# PWR_M_V1.net
KiCad netlist of a schematic drawn in Altium Designer
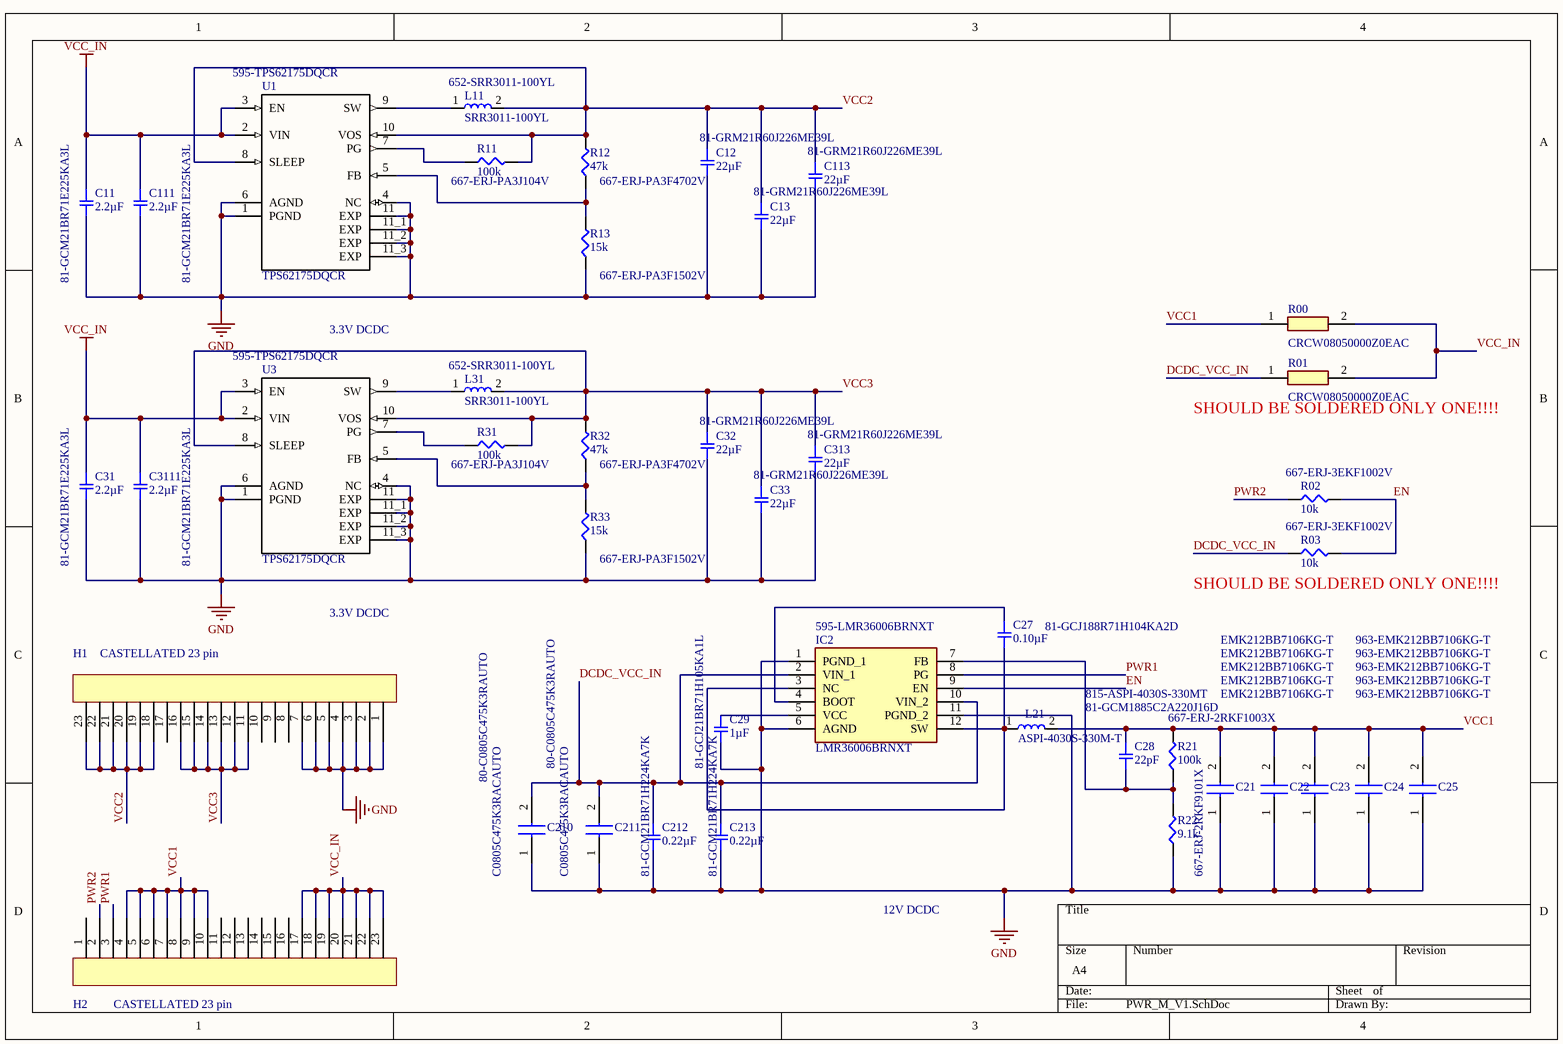
[diagram p0: PWR_M_V1.SchDoc]

(export (version "E")
  (design (tool "Eeschema 10.0.6"))
  (components
    (comp (ref "C11")
      (value "2.2µF")
      (footprint "SMD-0805C")
      (description "CAP CER 2.2UF 25V X7R 0805")
      (fields
        (field (name "DIGI-KEY PART NUMBER") "490-4787-1-ND")
        (field (name "PART NUMBER") "GCM21BR71E225KA73L")
        (field (name "SUPPLIER PART NUMBER 1") "81-GCM21BR71E225KA3L")
      )
      (libsource (lib "capacitor_murata_0805") (part "GCM21BR71E225KA73L"))
    )
    (comp (ref "C12")
      (value "22µF")
      (footprint "SMD-0805C")
      (description "CAP CER 22UF 6.3V X5R 0805")
      (fields
        (field (name "PART NUMBER") "GRM21BR60J226ME39L")
        (field (name "DIGI-KEY PART NUMBER") "490-1719-1-ND")
        (field (name "SUPPLIER PART NUMBER 1") "81-GRM21R60J226ME39L")
      )
      (libsource (lib "cap_murata") (part "CAPACITOR"))
    )
    (comp (ref "C13")
      (value "22µF")
      (footprint "SMD-0805C")
      (description "CAP CER 22UF 6.3V X5R 0805")
      (fields
        (field (name "PART NUMBER") "GRM21BR60J226ME39L")
        (field (name "DIGI-KEY PART NUMBER") "490-1719-1-ND")
        (field (name "SUPPLIER PART NUMBER 1") "81-GRM21R60J226ME39L")
      )
      (libsource (lib "cap_murata") (part "CAPACITOR"))
    )
    (comp (ref "C21")
      (value "EMK212BB7106KG-T")
      (footprint "SamacSys:CAPC2012X135N")
      (description "Capacitor")
      (fields (field (name "SUPPLIER PART NUMBER 1") "963-EMK212BB7106KG-T"))
      (libsource (lib "*") (part "EMK212BB7106KG-T"))
    )
    (comp (ref "C22")
      (value "EMK212BB7106KG-T")
      (footprint "SamacSys:CAPC2012X135N")
      (description "Capacitor")
      (fields (field (name "SUPPLIER PART NUMBER 1") "963-EMK212BB7106KG-T"))
      (libsource (lib "*") (part "EMK212BB7106KG-T"))
    )
    (comp (ref "C23")
      (value "EMK212BB7106KG-T")
      (footprint "SamacSys:CAPC2012X135N")
      (description "Capacitor")
      (fields (field (name "SUPPLIER PART NUMBER 1") "963-EMK212BB7106KG-T"))
      (libsource (lib "*") (part "EMK212BB7106KG-T"))
    )
    (comp (ref "C24")
      (value "EMK212BB7106KG-T")
      (footprint "SamacSys:CAPC2012X135N")
      (description "Capacitor")
      (fields (field (name "SUPPLIER PART NUMBER 1") "963-EMK212BB7106KG-T"))
      (libsource (lib "*") (part "EMK212BB7106KG-T"))
    )
    (comp (ref "C25")
      (value "EMK212BB7106KG-T")
      (footprint "SamacSys:CAPC2012X135N")
      (description "Capacitor")
      (fields (field (name "SUPPLIER PART NUMBER 1") "963-EMK212BB7106KG-T"))
      (libsource (lib "*") (part "EMK212BB7106KG-T"))
    )
    (comp (ref "C27")
      (value "0.10µF")
      (footprint "SMD-0603C")
      (description "CAP CER 0.1UF 50V X7R 0603")
      (fields
        (field (name "DIGI-KEY PART NUMBER") "490-5798-1-ND")
        (field (name "PART NUMBER") "GCJ188R71H104KA12D")
        (field (name "SUPPLIER PART NUMBER 1") "81-GCJ188R71H104KA2D")
      )
      (libsource (lib "capacitor_murata_0603") (part "GCJ188R71H104KA12D"))
    )
    (comp (ref "C28")
      (value "22pF")
      (footprint "SMD-0603C")
      (description "CAP CER 22PF 100V NP0 0603")
      (fields
        (field (name "DIGI-KEY PART NUMBER") "490-4942-1-ND")
        (field (name "PART NUMBER") "GCM1885C2A220JA16D")
        (field (name "SUPPLIER PART NUMBER 1") "81-GCM1885C2A220J16D")
      )
      (libsource (lib "capacitor_murata_0603") (part "GCM1885C2A220JA16D"))
    )
    (comp (ref "C29")
      (value "1µF")
      (footprint "SMD-0805C")
      (description "CAP CER 1UF 50V X7R 0805")
      (fields
        (field (name "DIGI-KEY PART NUMBER") "490-10667-1-ND")
        (field (name "PART NUMBER") "GCJ21BR71H105KA01L")
        (field (name "SUPPLIER PART NUMBER 1") "81-GCJ21BR71H105KA1L")
      )
      (libsource (lib "capacitor_murata_0805") (part "GCJ21BR71H105KA01L"))
    )
    (comp (ref "C31")
      (value "2.2µF")
      (footprint "SMD-0805C")
      (description "CAP CER 2.2UF 25V X7R 0805")
      (fields
        (field (name "DIGI-KEY PART NUMBER") "490-4787-1-ND")
        (field (name "PART NUMBER") "GCM21BR71E225KA73L")
        (field (name "SUPPLIER PART NUMBER 1") "81-GCM21BR71E225KA3L")
      )
      (libsource (lib "capacitor_murata_0805") (part "GCM21BR71E225KA73L"))
    )
    (comp (ref "C32")
      (value "22µF")
      (footprint "SMD-0805C")
      (description "CAP CER 22UF 6.3V X5R 0805")
      (fields
        (field (name "PART NUMBER") "GRM21BR60J226ME39L")
        (field (name "DIGI-KEY PART NUMBER") "490-1719-1-ND")
        (field (name "SUPPLIER PART NUMBER 1") "81-GRM21R60J226ME39L")
      )
      (libsource (lib "cap_murata") (part "CAPACITOR"))
    )
    (comp (ref "C33")
      (value "22µF")
      (footprint "SMD-0805C")
      (description "CAP CER 22UF 6.3V X5R 0805")
      (fields
        (field (name "PART NUMBER") "GRM21BR60J226ME39L")
        (field (name "DIGI-KEY PART NUMBER") "490-1719-1-ND")
        (field (name "SUPPLIER PART NUMBER 1") "81-GRM21R60J226ME39L")
      )
      (libsource (lib "cap_murata") (part "CAPACITOR"))
    )
    (comp (ref "C111")
      (value "2.2µF")
      (footprint "SMD-0805C")
      (description "CAP CER 2.2UF 25V X7R 0805")
      (fields
        (field (name "DIGI-KEY PART NUMBER") "490-4787-1-ND")
        (field (name "PART NUMBER") "GCM21BR71E225KA73L")
        (field (name "SUPPLIER PART NUMBER 1") "81-GCM21BR71E225KA3L")
      )
      (libsource (lib "capacitor_murata_0805") (part "GCM21BR71E225KA73L"))
    )
    (comp (ref "C113")
      (value "22µF")
      (footprint "SMD-0805C")
      (description "CAP CER 22UF 6.3V X5R 0805")
      (fields
        (field (name "PART NUMBER") "GRM21BR60J226ME39L")
        (field (name "DIGI-KEY PART NUMBER") "490-1719-1-ND")
        (field (name "SUPPLIER PART NUMBER 1") "81-GRM21R60J226ME39L")
      )
      (libsource (lib "cap_murata") (part "CAPACITOR"))
    )
    (comp (ref "C210")
      (value "C0805C475K3RACAUTO")
      (footprint "SamacSys:CAPC2012X125N")
      (description "Capacitor")
      (fields
        (field (name "MOUSER2 PART NUMBER") "80-C0805C475K3RAUTO")
        (field (name "SUPPLIER PART NUMBER 1") "80-C0805C475K3RAUTO")
      )
      (libsource (lib "*") (part "C0805C475K3RACAUTO"))
    )
    (comp (ref "C211")
      (value "C0805C475K3RACAUTO")
      (footprint "SamacSys:CAPC2012X125N")
      (description "Capacitor")
      (fields
        (field (name "MOUSER2 PART NUMBER") "80-C0805C475K3RAUTO")
        (field (name "SUPPLIER PART NUMBER 1") "80-C0805C475K3RAUTO")
      )
      (libsource (lib "*") (part "C0805C475K3RACAUTO"))
    )
    (comp (ref "C212")
      (value "0.22µF")
      (footprint "SMD-0805C")
      (description "CAP CER 0.22UF 50V X7R 0805")
      (fields
        (field (name "DIGI-KEY PART NUMBER") "490-13311-1-ND")
        (field (name "PART NUMBER") "GCM21BR71H224KA37K")
        (field (name "SUPPLIER PART NUMBER 1") "81-GCM21BR71H224KA7K")
      )
      (libsource (lib "capacitor_murata_0805") (part "GCM21BR71H224KA37K"))
    )
    (comp (ref "C213")
      (value "0.22µF")
      (footprint "SMD-0805C")
      (description "CAP CER 0.22UF 50V X7R 0805")
      (fields
        (field (name "DIGI-KEY PART NUMBER") "490-13311-1-ND")
        (field (name "PART NUMBER") "GCM21BR71H224KA37K")
        (field (name "SUPPLIER PART NUMBER 1") "81-GCM21BR71H224KA7K")
      )
      (libsource (lib "capacitor_murata_0805") (part "GCM21BR71H224KA37K"))
    )
    (comp (ref "C313")
      (value "22µF")
      (footprint "SMD-0805C")
      (description "CAP CER 22UF 6.3V X5R 0805")
      (fields
        (field (name "PART NUMBER") "GRM21BR60J226ME39L")
        (field (name "DIGI-KEY PART NUMBER") "490-1719-1-ND")
        (field (name "SUPPLIER PART NUMBER 1") "81-GRM21R60J226ME39L")
      )
      (libsource (lib "cap_murata") (part "CAPACITOR"))
    )
    (comp (ref "C3111")
      (value "2.2µF")
      (footprint "SMD-0805C")
      (description "CAP CER 2.2UF 25V X7R 0805")
      (fields
        (field (name "DIGI-KEY PART NUMBER") "490-4787-1-ND")
        (field (name "PART NUMBER") "GCM21BR71E225KA73L")
        (field (name "SUPPLIER PART NUMBER 1") "81-GCM21BR71E225KA3L")
      )
      (libsource (lib "capacitor_murata_0805") (part "GCM21BR71E225KA73L"))
    )
    (comp (ref "H1")
      (value "CASTELLATED 23 pin")
      (footprint "CASTELLATED 23 pin")
      (libsource (lib "USIB") (part "CASTELLATED 23 pin"))
    )
    (comp (ref "H2")
      (value "CASTELLATED 23 pin")
      (footprint "CASTELLATED 23 pin")
      (libsource (lib "") (part "CASTELLATED 23 pin_1"))
    )
    (comp (ref "IC2")
      (value "LMR36006BRNXT")
      (footprint "SamacSys:LMR36015FSCQRNXTQ1")
      (description "Integrated Circuit")
      (fields
        (field (name "MOUSER2 PART NUMBER") "595-LMR36006BRNXT")
        (field (name "SUPPLIER PART NUMBER 1") "595-LMR36006BRNXT")
      )
      (libsource (lib "*") (part "LMR36006BRNXT"))
    )
    (comp (ref "L11")
      (value "SRR3011-100YL")
      (footprint "SRR3011-100YL")
      (fields (field (name "SUPPLIER PART NUMBER 1") "652-SRR3011-100YL"))
      (libsource (lib "SRR3011-100YL") (part "SRR3011-100YL"))
    )
    (comp (ref "L21")
      (value "ASPI-4030S-330M-T")
      (footprint "INDPM4040X300N")
      (fields (field (name "SUPPLIER PART NUMBER 1") "815-ASPI-4030S-330MT"))
      (libsource (lib "SamacSys") (part "ASPI-4030S-330M-T"))
    )
    (comp (ref "L31")
      (value "SRR3011-100YL")
      (footprint "SRR3011-100YL")
      (fields (field (name "SUPPLIER PART NUMBER 1") "652-SRR3011-100YL"))
      (libsource (lib "SRR3011-100YL") (part "SRR3011-100YL"))
    )
    (comp (ref "R00")
      (value "CRCW08050000Z0EAC")
      (footprint "SamacSys:RESC2012X60N")
      (description "Resistor")
      (fields (field (name "MOUSER2 PART NUMBER") "71-CRCW08050000Z0EAC"))
      (libsource (lib "*") (part "CRCW08050000Z0EAC"))
    )
    (comp (ref "R01")
      (value "CRCW08050000Z0EAC")
      (footprint "SamacSys:RESC2012X60N")
      (description "Resistor")
      (fields (field (name "MOUSER2 PART NUMBER") "71-CRCW08050000Z0EAC"))
      (libsource (lib "*") (part "CRCW08050000Z0EAC"))
    )
    (comp (ref "R02")
      (value "10k")
      (footprint "SMD-0603-RES")
      (description "RES SMD 10K OHM 1% 1/10W 0603")
      (fields
        (field (name "PART NUMBER") "ERJ-3EKF1002V")
        (field (name "DIGI-KEY PART NUMBER") "P10.0KHCT-ND")
        (field (name "SUPPLIER PART NUMBER 1") "667-ERJ-3EKF1002V")
      )
      (libsource (lib "Panasonic_ERJ_0603") (part "ERJ-3EKF1002V"))
    )
    (comp (ref "R03")
      (value "10k")
      (footprint "SMD-0603-RES")
      (description "RES SMD 10K OHM 1% 1/10W 0603")
      (fields
        (field (name "PART NUMBER") "ERJ-3EKF1002V")
        (field (name "DIGI-KEY PART NUMBER") "P10.0KHCT-ND")
        (field (name "SUPPLIER PART NUMBER 1") "667-ERJ-3EKF1002V")
      )
      (libsource (lib "Panasonic_ERJ_0603") (part "ERJ-3EKF1002V"))
    )
    (comp (ref "R11")
      (value "100k")
      (footprint "SMD-0603-RES")
      (description "RES SMD 100K OHM 5% 1/4W 0603")
      (fields
        (field (name "PART NUMBER") "ERJ-PA3J104V")
        (field (name "DIGI-KEY PART NUMBER") "P100KBZCT-ND")
        (field (name "SUPPLIER PART NUMBER 1") "667-ERJ-PA3J104V")
      )
      (libsource (lib "Panasonic_ERJ_0603") (part "ERJ-PA3J104V"))
    )
    (comp (ref "R12")
      (value "47k")
      (footprint "SMD-0603-RES")
      (description "RES SMD 47K OHM 1% 1/4W 0603")
      (fields
        (field (name "PART NUMBER") "ERJ-PA3F4702V")
        (field (name "DIGI-KEY PART NUMBER") "P47KBYCT-ND")
        (field (name "SUPPLIER PART NUMBER 1") "667-ERJ-PA3F4702V")
      )
      (libsource (lib "Panasonic_ERJ_0603") (part "ERJ-PA3F4702V"))
    )
    (comp (ref "R13")
      (value "15k")
      (footprint "SMD-0603-RES")
      (description "RES SMD 15K OHM 1% 1/4W 0603")
      (fields
        (field (name "PART NUMBER") "ERJ-PA3F1502V")
        (field (name "DIGI-KEY PART NUMBER") "P15KBYCT-ND")
        (field (name "SUPPLIER PART NUMBER 1") "667-ERJ-PA3F1502V")
      )
      (libsource (lib "Panasonic_ERJ_0603") (part "ERJ-PA3F1502V"))
    )
    (comp (ref "R21")
      (value "100k")
      (footprint "SMD-0402-RES")
      (description "RES SMD 100K OHM 1% 1/10W 0402")
      (fields
        (field (name "PART NUMBER") "ERJ-2RKF1003X")
        (field (name "DIGI-KEY PART NUMBER") "P100KLCT-ND")
        (field (name "SUPPLIER PART NUMBER 1") "667-ERJ-2RKF1003X")
      )
      (libsource (lib "Panasonic_ERJ_0402") (part "ERJ-2RKF1003X"))
    )
    (comp (ref "R22")
      (value "9.1k")
      (footprint "SMD-0402-RES")
      (description "RES SMD 9.1K OHM 1% 1/10W 0402")
      (fields
        (field (name "PART NUMBER") "ERJ-2RKF9101X")
        (field (name "DIGI-KEY PART NUMBER") "P9.10KLCT-ND")
        (field (name "SUPPLIER PART NUMBER 1") "667-ERJ-2RKF9101X")
      )
      (libsource (lib "Panasonic_ERJ_0402") (part "ERJ-2RKF9101X"))
    )
    (comp (ref "R31")
      (value "100k")
      (footprint "SMD-0603-RES")
      (description "RES SMD 100K OHM 5% 1/4W 0603")
      (fields
        (field (name "PART NUMBER") "ERJ-PA3J104V")
        (field (name "DIGI-KEY PART NUMBER") "P100KBZCT-ND")
        (field (name "SUPPLIER PART NUMBER 1") "667-ERJ-PA3J104V")
      )
      (libsource (lib "Panasonic_ERJ_0603") (part "ERJ-PA3J104V"))
    )
    (comp (ref "R32")
      (value "47k")
      (footprint "SMD-0603-RES")
      (description "RES SMD 47K OHM 1% 1/4W 0603")
      (fields
        (field (name "PART NUMBER") "ERJ-PA3F4702V")
        (field (name "DIGI-KEY PART NUMBER") "P47KBYCT-ND")
        (field (name "SUPPLIER PART NUMBER 1") "667-ERJ-PA3F4702V")
      )
      (libsource (lib "Panasonic_ERJ_0603") (part "ERJ-PA3F4702V"))
    )
    (comp (ref "R33")
      (value "15k")
      (footprint "SMD-0603-RES")
      (description "RES SMD 15K OHM 1% 1/4W 0603")
      (fields
        (field (name "PART NUMBER") "ERJ-PA3F1502V")
        (field (name "DIGI-KEY PART NUMBER") "P15KBYCT-ND")
        (field (name "SUPPLIER PART NUMBER 1") "667-ERJ-PA3F1502V")
      )
      (libsource (lib "Panasonic_ERJ_0603") (part "ERJ-PA3F1502V"))
    )
    (comp (ref "U1")
      (value "TPS62175DQCR")
      (footprint "*SON50P300X200X80-11N240X84_TPS62175DQCR(Primary)")
      (description "28V, 0.5A Step-Down Converter with SNOOZE Mode 10-WSON -40 to 85")
      (fields
        (field (name "MF") "Texas Instruments")
        (field (name "SUPPLIER PART NUMBER 1") "595-TPS62175DQCR")
      )
      (libsource (lib "TPS62175DQCR") (part "TPS62175DQCR"))
    )
    (comp (ref "U3")
      (value "TPS62175DQCR")
      (footprint "*SON50P300X200X80-11N240X84_TPS62175DQCR(Primary)")
      (description "28V, 0.5A Step-Down Converter with SNOOZE Mode 10-WSON -40 to 85")
      (fields
        (field (name "MF") "Texas Instruments")
        (field (name "SUPPLIER PART NUMBER 1") "595-TPS62175DQCR")
      )
      (libsource (lib "TPS62175DQCR") (part "TPS62175DQCR"))
    )
  )
  (nets
    (net (code "1") (name "/DCDC_VCC_IN") (class "Default")
      (node (ref "C210") (pin "2") (pinfunction "2_2") (pintype "passive"))
      (node (ref "C211") (pin "2") (pinfunction "2_2") (pintype "passive"))
      (node (ref "C212") (pin "1") (pinfunction "1_1") (pintype "passive"))
      (node (ref "C213") (pin "1") (pinfunction "1_1") (pintype "passive"))
      (node (ref "IC2") (pin "10") (pinfunction "VIN_2_10") (pintype "passive"))
      (node (ref "IC2") (pin "2") (pinfunction "VIN_1_2") (pintype "passive"))
      (node (ref "R01") (pin "1") (pinfunction "1_1") (pintype "passive"))
      (node (ref "R03") (pin "1") (pinfunction "1_1") (pintype "passive"))
    )
    (net (code "2") (name "/EN") (class "Default")
      (node (ref "IC2") (pin "9") (pinfunction "EN_9") (pintype "passive"))
      (node (ref "R02") (pin "2") (pinfunction "2_2") (pintype "passive"))
      (node (ref "R03") (pin "2") (pinfunction "2_2") (pintype "passive"))
    )
    (net (code "3") (name "/PWR1") (class "Default")
      (node (ref "H2") (pin "3") (pintype "passive"))
      (node (ref "IC2") (pin "8") (pinfunction "PG_8") (pintype "passive"))
    )
    (net (code "4") (name "/PWR2") (class "Default")
      (node (ref "H2") (pin "2") (pintype "passive"))
      (node (ref "R02") (pin "1") (pinfunction "1_1") (pintype "passive"))
    )
    (net (code "5") (name "/VCC1") (class "Default")
      (node (ref "C21") (pin "2") (pinfunction "2_2") (pintype "passive"))
      (node (ref "C22") (pin "2") (pinfunction "2_2") (pintype "passive"))
      (node (ref "C23") (pin "2") (pinfunction "2_2") (pintype "passive"))
      (node (ref "C24") (pin "2") (pinfunction "2_2") (pintype "passive"))
      (node (ref "C25") (pin "2") (pinfunction "2_2") (pintype "passive"))
      (node (ref "C28") (pin "1") (pinfunction "1_1") (pintype "passive"))
      (node (ref "H2") (pin "10") (pintype "passive"))
      (node (ref "H2") (pin "4") (pintype "passive"))
      (node (ref "H2") (pin "5") (pintype "passive"))
      (node (ref "H2") (pin "6") (pintype "passive"))
      (node (ref "H2") (pin "7") (pintype "passive"))
      (node (ref "H2") (pin "8") (pintype "passive"))
      (node (ref "H2") (pin "9") (pintype "passive"))
      (node (ref "L21") (pin "2") (pinfunction "2_2") (pintype "passive"))
      (node (ref "R00") (pin "1") (pinfunction "1_1") (pintype "passive"))
      (node (ref "R21") (pin "2") (pinfunction "2_2") (pintype "passive"))
    )
    (net (code "6") (name "/VCC2") (class "Default")
      (node (ref "C113") (pin "1") (pinfunction "1_1") (pintype "passive"))
      (node (ref "C12") (pin "1") (pinfunction "1_1") (pintype "passive"))
      (node (ref "C13") (pin "1") (pinfunction "1_1") (pintype "passive"))
      (node (ref "H1") (pin "18") (pintype "passive"))
      (node (ref "H1") (pin "19") (pintype "passive"))
      (node (ref "H1") (pin "20") (pintype "passive"))
      (node (ref "H1") (pin "21") (pintype "passive"))
      (node (ref "H1") (pin "22") (pintype "passive"))
      (node (ref "H1") (pin "23") (pintype "passive"))
      (node (ref "L11") (pin "2") (pinfunction "2_2") (pintype "passive"))
      (node (ref "R11") (pin "2") (pinfunction "2_2") (pintype "passive"))
      (node (ref "R12") (pin "2") (pinfunction "2_2") (pintype "passive"))
      (node (ref "U1") (pin "10") (pinfunction "VOS_10") (pintype "input"))
      (node (ref "U1") (pin "8") (pinfunction "SLEEP_8") (pintype "input"))
    )
    (net (code "7") (name "/VCC3") (class "Default")
      (node (ref "C313") (pin "1") (pinfunction "1_1") (pintype "passive"))
      (node (ref "C32") (pin "1") (pinfunction "1_1") (pintype "passive"))
      (node (ref "C33") (pin "1") (pinfunction "1_1") (pintype "passive"))
      (node (ref "H1") (pin "11") (pintype "passive"))
      (node (ref "H1") (pin "12") (pintype "passive"))
      (node (ref "H1") (pin "13") (pintype "passive"))
      (node (ref "H1") (pin "14") (pintype "passive"))
      (node (ref "H1") (pin "15") (pintype "passive"))
      (node (ref "H1") (pin "16") (pintype "passive"))
      (node (ref "L31") (pin "2") (pinfunction "2_2") (pintype "passive"))
      (node (ref "R31") (pin "2") (pinfunction "2_2") (pintype "passive"))
      (node (ref "R32") (pin "2") (pinfunction "2_2") (pintype "passive"))
      (node (ref "U3") (pin "10") (pinfunction "VOS_10") (pintype "input"))
      (node (ref "U3") (pin "8") (pinfunction "SLEEP_8") (pintype "input"))
    )
    (net (code "8") (name "GND") (class "Default")
      (node (ref "C11") (pin "2") (pinfunction "2_2") (pintype "passive"))
      (node (ref "C111") (pin "2") (pinfunction "2_2") (pintype "passive"))
      (node (ref "C113") (pin "2") (pinfunction "2_2") (pintype "passive"))
      (node (ref "C12") (pin "2") (pinfunction "2_2") (pintype "passive"))
      (node (ref "C13") (pin "2") (pinfunction "2_2") (pintype "passive"))
      (node (ref "C21") (pin "1") (pinfunction "1_1") (pintype "passive"))
      (node (ref "C210") (pin "1") (pinfunction "1_1") (pintype "passive"))
      (node (ref "C211") (pin "1") (pinfunction "1_1") (pintype "passive"))
      (node (ref "C212") (pin "2") (pinfunction "2_2") (pintype "passive"))
      (node (ref "C213") (pin "2") (pinfunction "2_2") (pintype "passive"))
      (node (ref "C22") (pin "1") (pinfunction "1_1") (pintype "passive"))
      (node (ref "C23") (pin "1") (pinfunction "1_1") (pintype "passive"))
      (node (ref "C24") (pin "1") (pinfunction "1_1") (pintype "passive"))
      (node (ref "C25") (pin "1") (pinfunction "1_1") (pintype "passive"))
      (node (ref "C29") (pin "2") (pinfunction "2_2") (pintype "passive"))
      (node (ref "C31") (pin "2") (pinfunction "2_2") (pintype "passive"))
      (node (ref "C3111") (pin "2") (pinfunction "2_2") (pintype "passive"))
      (node (ref "C313") (pin "2") (pinfunction "2_2") (pintype "passive"))
      (node (ref "C32") (pin "2") (pinfunction "2_2") (pintype "passive"))
      (node (ref "C33") (pin "2") (pinfunction "2_2") (pintype "passive"))
      (node (ref "H1") (pin "1") (pintype "passive"))
      (node (ref "H1") (pin "2") (pintype "passive"))
      (node (ref "H1") (pin "3") (pintype "passive"))
      (node (ref "H1") (pin "4") (pintype "passive"))
      (node (ref "H1") (pin "5") (pintype "passive"))
      (node (ref "H1") (pin "6") (pintype "passive"))
      (node (ref "H1") (pin "7") (pintype "passive"))
      (node (ref "IC2") (pin "1") (pinfunction "PGND_1_1") (pintype "passive"))
      (node (ref "IC2") (pin "11") (pinfunction "PGND_2_11") (pintype "passive"))
      (node (ref "IC2") (pin "6") (pinfunction "AGND_6") (pintype "passive"))
      (node (ref "R13") (pin "1") (pinfunction "1_1") (pintype "passive"))
      (node (ref "R22") (pin "1") (pinfunction "1_1") (pintype "passive"))
      (node (ref "R33") (pin "1") (pinfunction "1_1") (pintype "passive"))
      (node (ref "U1") (pin "1") (pinfunction "PGND_1") (pintype "power_in"))
      (node (ref "U1") (pin "11") (pinfunction "EXP_11") (pintype "power_in"))
      (node (ref "U1") (pin "11_1") (pinfunction "EXP_11_1") (pintype "power_in"))
      (node (ref "U1") (pin "11_2") (pinfunction "EXP_11_2") (pintype "power_in"))
      (node (ref "U1") (pin "11_3") (pinfunction "EXP_11_3") (pintype "power_in"))
      (node (ref "U1") (pin "4") (pinfunction "NC_4") (pintype "bidirectional"))
      (node (ref "U1") (pin "6") (pinfunction "AGND_6") (pintype "power_in"))
      (node (ref "U3") (pin "1") (pinfunction "PGND_1") (pintype "power_in"))
      (node (ref "U3") (pin "11") (pinfunction "EXP_11") (pintype "power_in"))
      (node (ref "U3") (pin "11_1") (pinfunction "EXP_11_1") (pintype "power_in"))
      (node (ref "U3") (pin "11_2") (pinfunction "EXP_11_2") (pintype "power_in"))
      (node (ref "U3") (pin "11_3") (pinfunction "EXP_11_3") (pintype "power_in"))
      (node (ref "U3") (pin "4") (pinfunction "NC_4") (pintype "bidirectional"))
      (node (ref "U3") (pin "6") (pinfunction "AGND_6") (pintype "power_in"))
    )
    (net (code "9") (name "Net-(IC2-BOOT)") (class "Default")
      (node (ref "C27") (pin "1") (pinfunction "1_1") (pintype "passive"))
      (node (ref "IC2") (pin "4") (pinfunction "BOOT_4") (pintype "passive"))
    )
    (net (code "10") (name "Net-(IC2-FB)") (class "Default")
      (node (ref "C28") (pin "2") (pinfunction "2_2") (pintype "passive"))
      (node (ref "IC2") (pin "7") (pinfunction "FB_7") (pintype "passive"))
      (node (ref "R21") (pin "1") (pinfunction "1_1") (pintype "passive"))
      (node (ref "R22") (pin "2") (pinfunction "2_2") (pintype "passive"))
    )
    (net (code "11") (name "Net-(IC2-NC)") (class "Default")
      (node (ref "C27") (pin "2") (pinfunction "2_2") (pintype "passive"))
      (node (ref "IC2") (pin "12") (pinfunction "SW_12") (pintype "passive"))
      (node (ref "IC2") (pin "3") (pinfunction "NC_3") (pintype "passive"))
      (node (ref "L21") (pin "1") (pinfunction "1_1") (pintype "passive"))
    )
    (net (code "12") (name "Net-(IC2-VCC)") (class "Default")
      (node (ref "C29") (pin "1") (pinfunction "1_1") (pintype "passive"))
      (node (ref "IC2") (pin "5") (pinfunction "VCC_5") (pintype "passive"))
    )
    (net (code "13") (name "Net-(U1-FB)") (class "Default")
      (node (ref "R12") (pin "1") (pinfunction "1_1") (pintype "passive"))
      (node (ref "R13") (pin "2") (pinfunction "2_2") (pintype "passive"))
      (node (ref "U1") (pin "5") (pinfunction "FB_5") (pintype "input"))
    )
    (net (code "14") (name "Net-(U1-PG)") (class "Default")
      (node (ref "R11") (pin "1") (pinfunction "1_1") (pintype "passive"))
      (node (ref "U1") (pin "7") (pinfunction "PG_7") (pintype "output"))
    )
    (net (code "15") (name "Net-(U1-SW)") (class "Default")
      (node (ref "L11") (pin "1") (pinfunction "1_1") (pintype "passive"))
      (node (ref "U1") (pin "9") (pinfunction "SW_9") (pintype "output"))
    )
    (net (code "16") (name "Net-(U3-FB)") (class "Default")
      (node (ref "R32") (pin "1") (pinfunction "1_1") (pintype "passive"))
      (node (ref "R33") (pin "2") (pinfunction "2_2") (pintype "passive"))
      (node (ref "U3") (pin "5") (pinfunction "FB_5") (pintype "input"))
    )
    (net (code "17") (name "Net-(U3-PG)") (class "Default")
      (node (ref "R31") (pin "1") (pinfunction "1_1") (pintype "passive"))
      (node (ref "U3") (pin "7") (pinfunction "PG_7") (pintype "output"))
    )
    (net (code "18") (name "Net-(U3-SW)") (class "Default")
      (node (ref "L31") (pin "1") (pinfunction "1_1") (pintype "passive"))
      (node (ref "U3") (pin "9") (pinfunction "SW_9") (pintype "output"))
    )
    (net (code "19") (name "VCC_IN") (class "Default")
      (node (ref "C11") (pin "1") (pinfunction "1_1") (pintype "passive"))
      (node (ref "C111") (pin "1") (pinfunction "1_1") (pintype "passive"))
      (node (ref "C31") (pin "1") (pinfunction "1_1") (pintype "passive"))
      (node (ref "C3111") (pin "1") (pinfunction "1_1") (pintype "passive"))
      (node (ref "H2") (pin "17") (pintype "passive"))
      (node (ref "H2") (pin "18") (pintype "passive"))
      (node (ref "H2") (pin "19") (pintype "passive"))
      (node (ref "H2") (pin "20") (pintype "passive"))
      (node (ref "H2") (pin "21") (pintype "passive"))
      (node (ref "H2") (pin "22") (pintype "passive"))
      (node (ref "H2") (pin "23") (pintype "passive"))
      (node (ref "R00") (pin "2") (pinfunction "2_2") (pintype "passive"))
      (node (ref "R01") (pin "2") (pinfunction "2_2") (pintype "passive"))
      (node (ref "U1") (pin "2") (pinfunction "VIN_2") (pintype "input"))
      (node (ref "U1") (pin "3") (pinfunction "EN_3") (pintype "input"))
      (node (ref "U3") (pin "2") (pinfunction "VIN_2") (pintype "input"))
      (node (ref "U3") (pin "3") (pinfunction "EN_3") (pintype "input"))
    )
    (net (code "20") (name "unconnected-(H1-Pad8)") (class "Default")
      (node (ref "H1") (pin "8") (pintype "passive"))
    )
    (net (code "21") (name "unconnected-(H1-Pad9)") (class "Default")
      (node (ref "H1") (pin "9") (pintype "passive"))
    )
    (net (code "22") (name "unconnected-(H1-Pad10)") (class "Default")
      (node (ref "H1") (pin "10") (pintype "passive"))
    )
    (net (code "23") (name "unconnected-(H1-Pad17)") (class "Default")
      (node (ref "H1") (pin "17") (pintype "passive"))
    )
    (net (code "24") (name "unconnected-(H2-Pad1)") (class "Default")
      (node (ref "H2") (pin "1") (pintype "passive"))
    )
    (net (code "25") (name "unconnected-(H2-Pad11)") (class "Default")
      (node (ref "H2") (pin "11") (pintype "passive"))
    )
    (net (code "26") (name "unconnected-(H2-Pad12)") (class "Default")
      (node (ref "H2") (pin "12") (pintype "passive"))
    )
    (net (code "27") (name "unconnected-(H2-Pad13)") (class "Default")
      (node (ref "H2") (pin "13") (pintype "passive"))
    )
    (net (code "28") (name "unconnected-(H2-Pad14)") (class "Default")
      (node (ref "H2") (pin "14") (pintype "passive"))
    )
    (net (code "29") (name "unconnected-(H2-Pad15)") (class "Default")
      (node (ref "H2") (pin "15") (pintype "passive"))
    )
    (net (code "30") (name "unconnected-(H2-Pad16)") (class "Default")
      (node (ref "H2") (pin "16") (pintype "passive"))
    )
  )
)
